# 60W_24V_to_12V_Flyback.net
KiCad netlist of a schematic drawn in EAGLE
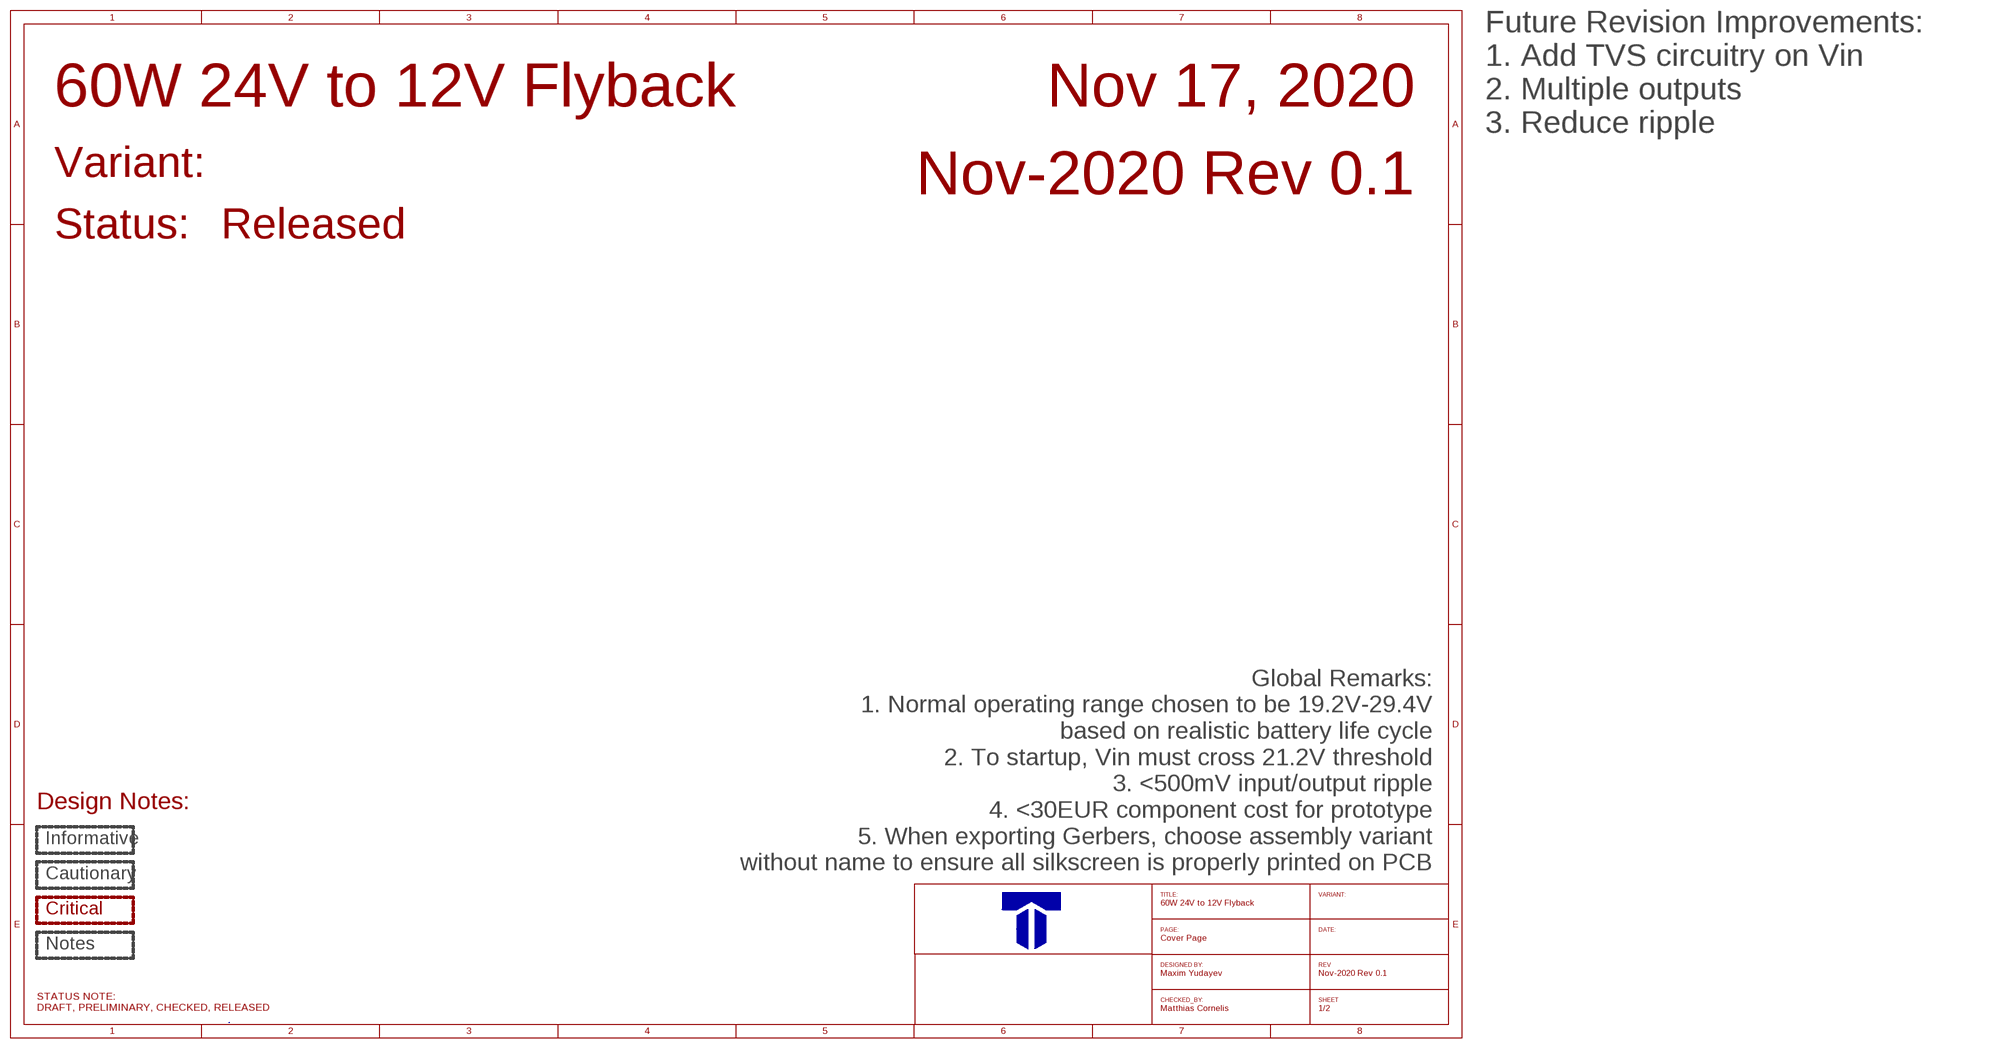
[diagram p0: schematic, sheet 1]
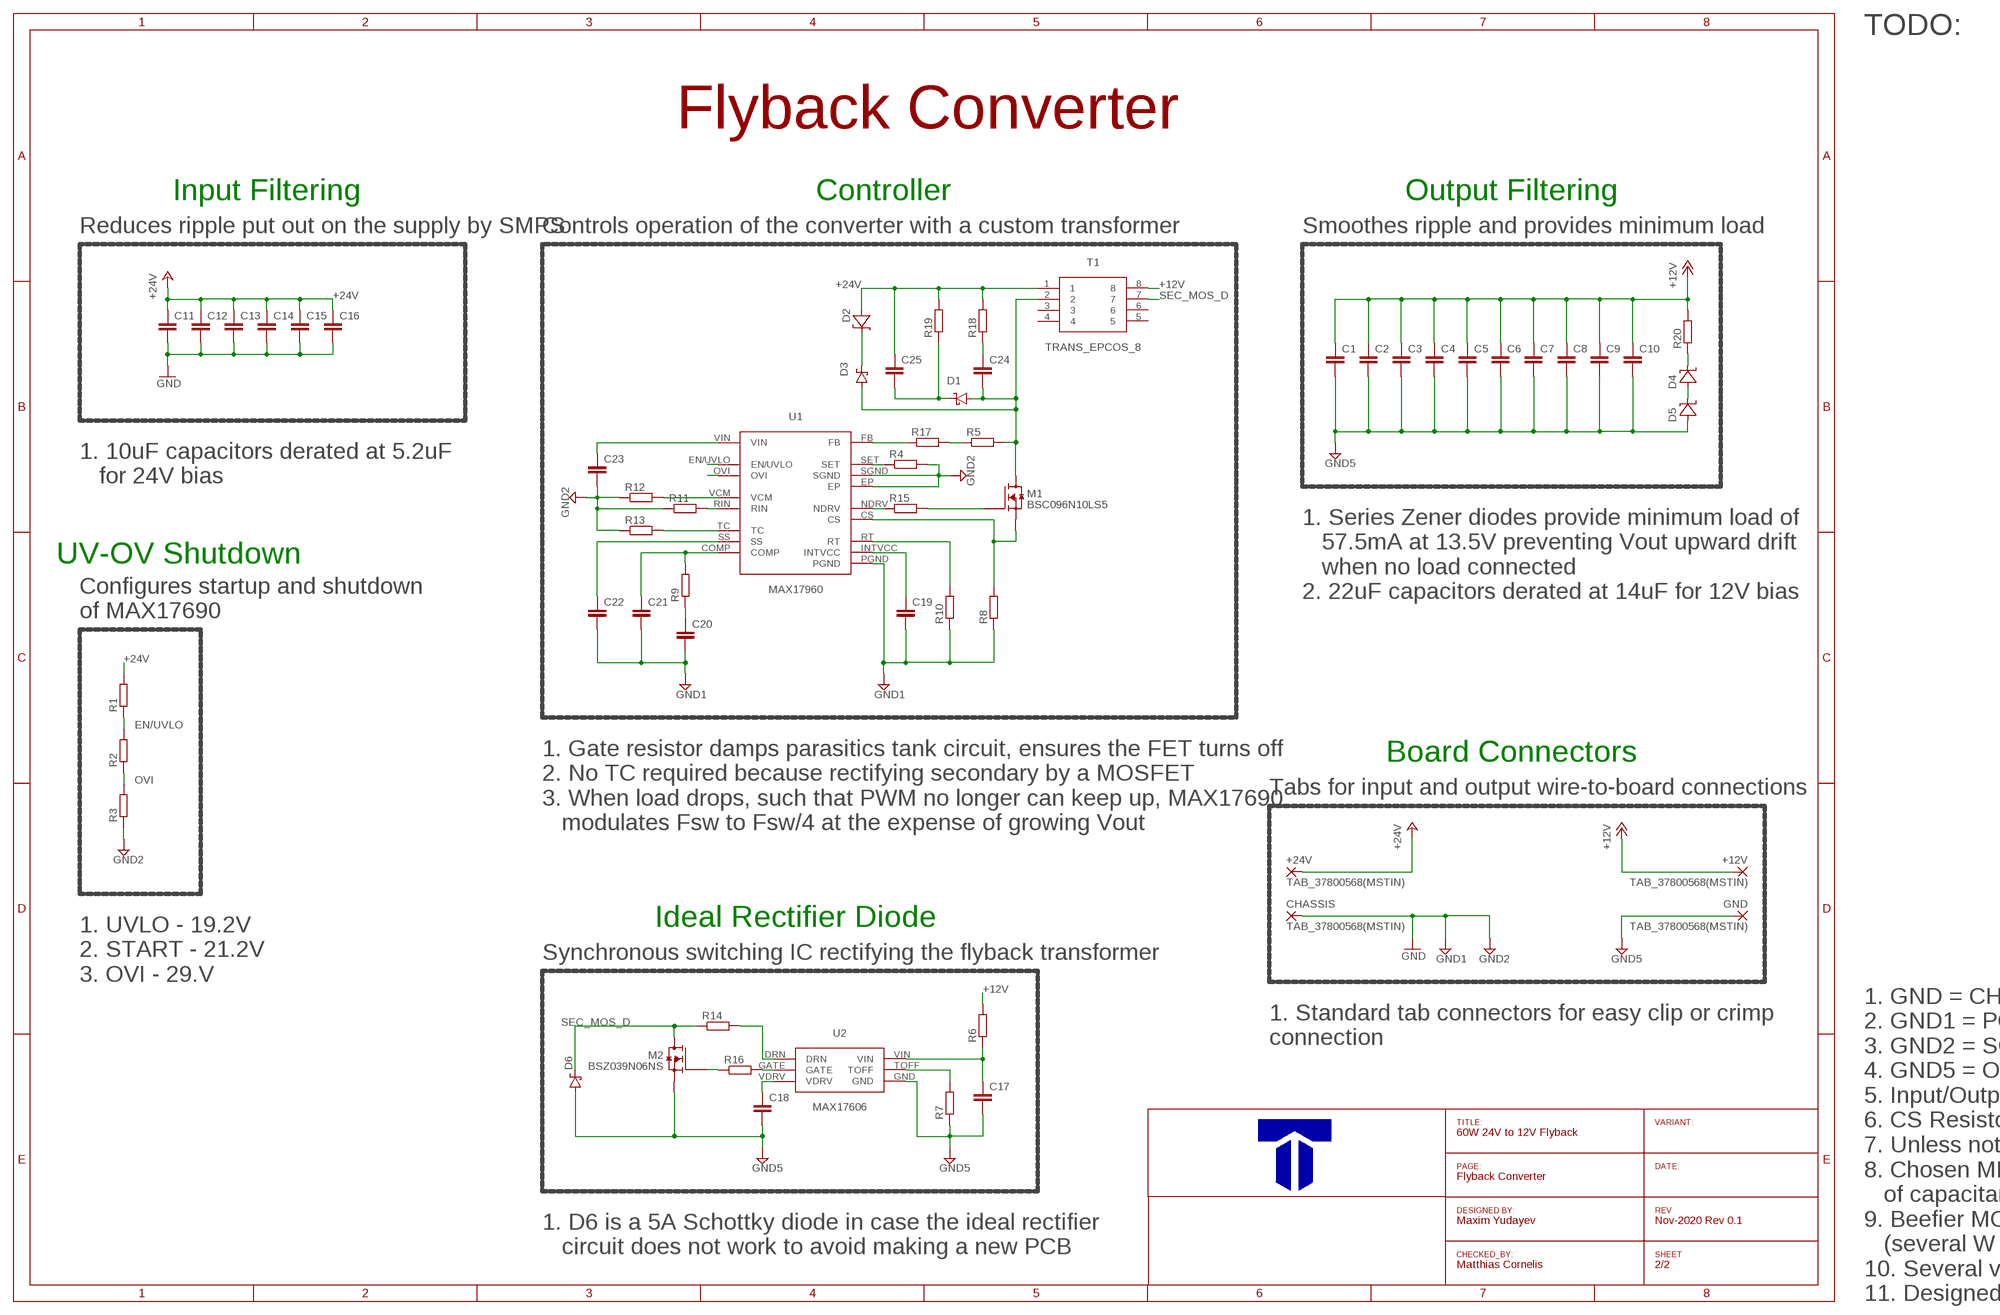
[diagram p1: schematic, sheet 2, part 1 of 2]
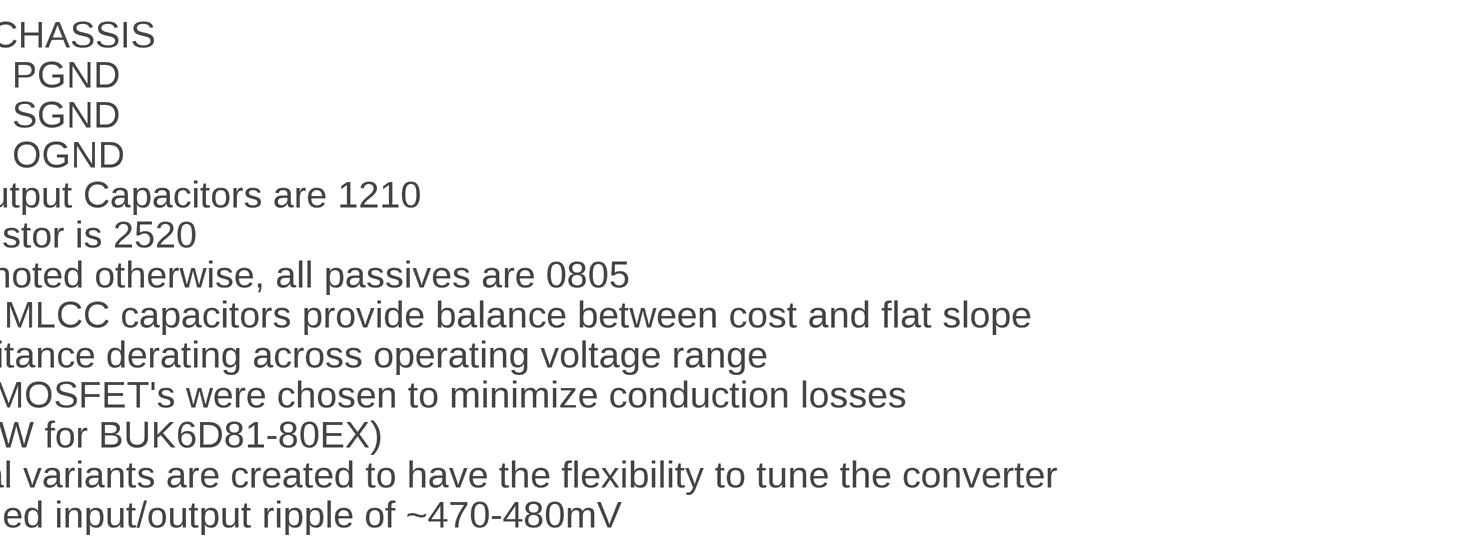
[diagram p2: schematic, sheet 2, part 2 of 2]

(export (version "E")
  (design (tool "Eeschema 10.0.6"))
  (components
    (comp (ref "+12V")
      (value "TAB_37800568(MSTIN)")
      (footprint "eagle-import:HOLE_1-3")
      (libsource (lib "eagle-import") (part "TAB_37800568(MSTIN)"))
    )
    (comp (ref "+24V")
      (value "TAB_37800568(MSTIN)")
      (footprint "eagle-import:HOLE_1-3")
      (libsource (lib "eagle-import") (part "TAB_37800568(MSTIN)"))
    )
    (comp (ref "C1")
      (value "C-EUC1210K")
      (footprint "eagle-import:C1210K")
      (libsource (lib "eagle-import") (part "C-EUC1210K"))
    )
    (comp (ref "C2")
      (value "C-EUC1210K")
      (footprint "eagle-import:C1210K")
      (libsource (lib "eagle-import") (part "C-EUC1210K"))
    )
    (comp (ref "C3")
      (value "C-EUC1210K")
      (footprint "eagle-import:C1210K")
      (libsource (lib "eagle-import") (part "C-EUC1210K"))
    )
    (comp (ref "C4")
      (value "C-EUC1210K")
      (footprint "eagle-import:C1210K")
      (libsource (lib "eagle-import") (part "C-EUC1210K"))
    )
    (comp (ref "C5")
      (value "C-EUC1210K")
      (footprint "eagle-import:C1210K")
      (libsource (lib "eagle-import") (part "C-EUC1210K"))
    )
    (comp (ref "C6")
      (value "C-EUC1210K")
      (footprint "eagle-import:C1210K")
      (libsource (lib "eagle-import") (part "C-EUC1210K"))
    )
    (comp (ref "C7")
      (value "C-EUC1210K")
      (footprint "eagle-import:C1210K")
      (libsource (lib "eagle-import") (part "C-EUC1210K"))
    )
    (comp (ref "C8")
      (value "C-EUC1210K")
      (footprint "eagle-import:C1210K")
      (libsource (lib "eagle-import") (part "C-EUC1210K"))
    )
    (comp (ref "C9")
      (value "C-EUC1210K")
      (footprint "eagle-import:C1210K")
      (libsource (lib "eagle-import") (part "C-EUC1210K"))
    )
    (comp (ref "C10")
      (value "C-EUC1210K")
      (footprint "eagle-import:C1210K")
      (libsource (lib "eagle-import") (part "C-EUC1210K"))
    )
    (comp (ref "C11")
      (value "C-EUC1210K")
      (footprint "eagle-import:C1210K")
      (libsource (lib "eagle-import") (part "C-EUC1210K"))
    )
    (comp (ref "C12")
      (value "C-EUC1210K")
      (footprint "eagle-import:C1210K")
      (libsource (lib "eagle-import") (part "C-EUC1210K"))
    )
    (comp (ref "C13")
      (value "C-EUC1210K")
      (footprint "eagle-import:C1210K")
      (libsource (lib "eagle-import") (part "C-EUC1210K"))
    )
    (comp (ref "C14")
      (value "C-EUC1210K")
      (footprint "eagle-import:C1210K")
      (libsource (lib "eagle-import") (part "C-EUC1210K"))
    )
    (comp (ref "C15")
      (value "C-EUC1210K")
      (footprint "eagle-import:C1210K")
      (libsource (lib "eagle-import") (part "C-EUC1210K"))
    )
    (comp (ref "C16")
      (value "C-EUC1210K")
      (footprint "eagle-import:C1210K")
      (libsource (lib "eagle-import") (part "C-EUC1210K"))
    )
    (comp (ref "C17")
      (value "C-EUC0805K")
      (footprint "eagle-import:C0805K")
      (libsource (lib "eagle-import") (part "C-EUC0805K"))
    )
    (comp (ref "C18")
      (value "C-EUC0805K")
      (footprint "eagle-import:C0805K")
      (libsource (lib "eagle-import") (part "C-EUC0805K"))
    )
    (comp (ref "C19")
      (value "C-EUC0805K")
      (footprint "eagle-import:C0805K")
      (libsource (lib "eagle-import") (part "C-EUC0805K"))
    )
    (comp (ref "C20")
      (value "C-EUC0805K")
      (footprint "eagle-import:C0805K")
      (libsource (lib "eagle-import") (part "C-EUC0805K"))
    )
    (comp (ref "C21")
      (value "C-EUC0805K")
      (footprint "eagle-import:C0805K")
      (libsource (lib "eagle-import") (part "C-EUC0805K"))
    )
    (comp (ref "C22")
      (value "C-EUC0805K")
      (footprint "eagle-import:C0805K")
      (libsource (lib "eagle-import") (part "C-EUC0805K"))
    )
    (comp (ref "C23")
      (value "C-EUC0805K")
      (footprint "eagle-import:C0805K")
      (libsource (lib "eagle-import") (part "C-EUC0805K"))
    )
    (comp (ref "C24")
      (value "C-EUC0805K")
      (footprint "eagle-import:C0805K")
      (libsource (lib "eagle-import") (part "C-EUC0805K"))
    )
    (comp (ref "C25")
      (value "C-EUC0805K")
      (footprint "eagle-import:C0805K")
      (libsource (lib "eagle-import") (part "C-EUC0805K"))
    )
    (comp (ref "CHASSIS")
      (value "TAB_37800568(MSTIN)")
      (footprint "eagle-import:HOLE_1-3")
      (libsource (lib "eagle-import") (part "TAB_37800568(MSTIN)"))
    )
    (comp (ref "D1")
      (value "DFLS2100-7")
      (footprint "eagle-import:DFLS2100_DS31475")
      (libsource (lib "eagle-import") (part "DFLS2100-7"))
    )
    (comp (ref "D2")
      (value "MMSZ5270BT1G")
      (footprint "eagle-import:MMSZ_T1G_SOD-123_425-04")
      (libsource (lib "eagle-import") (part "MMSZ52?T1G70B"))
    )
    (comp (ref "D3")
      (value "DFLS2100-7")
      (footprint "eagle-import:DFLS2100_DS31475")
      (libsource (lib "eagle-import") (part "DFLS2100-7"))
    )
    (comp (ref "D4")
      (value "MMSZ4692T1G")
      (footprint "eagle-import:MMSZ_T1G_SOD-123_425-04")
      (libsource (lib "eagle-import") (part "MMSZ4?T1G692"))
    )
    (comp (ref "D5")
      (value "MMSZ4692T1G")
      (footprint "eagle-import:MMSZ_T1G_SOD-123_425-04")
      (libsource (lib "eagle-import") (part "MMSZ4?T1G692"))
    )
    (comp (ref "D6")
      (value "B540C-13-F")
      (footprint "eagle-import:B5_0C-13-F_DO-214AB_DS13012")
      (libsource (lib "eagle-import") (part "B5?0C-13-F4"))
    )
    (comp (ref "GND")
      (value "TAB_37800568(MSTIN)")
      (footprint "eagle-import:HOLE_1-3")
      (libsource (lib "eagle-import") (part "TAB_37800568(MSTIN)"))
    )
    (comp (ref "M1")
      (value "BSC096N10LS5")
      (footprint "eagle-import:BSC096N10LS5_TDSON-8")
      (libsource (lib "eagle-import") (part "BSC096N10LS5"))
    )
    (comp (ref "M2")
      (value "BSZ039N06NS")
      (footprint "eagle-import:BSZ039N06NS_TSDSON-8_Z8B00158553")
      (libsource (lib "eagle-import") (part "BSZ039N06NS"))
    )
    (comp (ref "R1")
      (value "R-EU_R0805")
      (footprint "eagle-import:R0805")
      (libsource (lib "eagle-import") (part "R-EU_R0805"))
    )
    (comp (ref "R2")
      (value "R-EU_R0805")
      (footprint "eagle-import:R0805")
      (libsource (lib "eagle-import") (part "R-EU_R0805"))
    )
    (comp (ref "R3")
      (value "R-EU_R0805")
      (footprint "eagle-import:R0805")
      (libsource (lib "eagle-import") (part "R-EU_R0805"))
    )
    (comp (ref "R4")
      (value "R-EU_R0805")
      (footprint "eagle-import:R0805")
      (libsource (lib "eagle-import") (part "R-EU_R0805"))
    )
    (comp (ref "R5")
      (value "R-EU_R0805")
      (footprint "eagle-import:R0805")
      (libsource (lib "eagle-import") (part "R-EU_R0805"))
    )
    (comp (ref "R6")
      (value "R-EU_R0805")
      (footprint "eagle-import:R0805")
      (libsource (lib "eagle-import") (part "R-EU_R0805"))
    )
    (comp (ref "R7")
      (value "R-EU_R0805")
      (footprint "eagle-import:R0805")
      (libsource (lib "eagle-import") (part "R-EU_R0805"))
    )
    (comp (ref "R8")
      (value "R-EU_R2512")
      (footprint "eagle-import:R2512")
      (libsource (lib "eagle-import") (part "R-EU_R2512"))
    )
    (comp (ref "R9")
      (value "R-EU_R0805")
      (footprint "eagle-import:R0805")
      (libsource (lib "eagle-import") (part "R-EU_R0805"))
    )
    (comp (ref "R10")
      (value "R-EU_R0805")
      (footprint "eagle-import:R0805")
      (libsource (lib "eagle-import") (part "R-EU_R0805"))
    )
    (comp (ref "R11")
      (value "R-EU_R0805")
      (footprint "eagle-import:R0805")
      (libsource (lib "eagle-import") (part "R-EU_R0805"))
    )
    (comp (ref "R12")
      (value "R-EU_R0805")
      (footprint "eagle-import:R0805")
      (libsource (lib "eagle-import") (part "R-EU_R0805"))
    )
    (comp (ref "R13")
      (value "R-EU_R0805")
      (footprint "eagle-import:R0805")
      (libsource (lib "eagle-import") (part "R-EU_R0805"))
    )
    (comp (ref "R14")
      (value "R-EU_R0805")
      (footprint "eagle-import:R0805")
      (libsource (lib "eagle-import") (part "R-EU_R0805"))
    )
    (comp (ref "R15")
      (value "R-EU_R0805")
      (footprint "eagle-import:R0805")
      (libsource (lib "eagle-import") (part "R-EU_R0805"))
    )
    (comp (ref "R16")
      (value "R-EU_R0805")
      (footprint "eagle-import:R0805")
      (libsource (lib "eagle-import") (part "R-EU_R0805"))
    )
    (comp (ref "R17")
      (value "R-EU_R0805")
      (footprint "eagle-import:R0805")
      (libsource (lib "eagle-import") (part "R-EU_R0805"))
    )
    (comp (ref "R18")
      (value "R-EU_R0805")
      (footprint "eagle-import:R0805")
      (libsource (lib "eagle-import") (part "R-EU_R0805"))
    )
    (comp (ref "R19")
      (value "R-EU_R0805")
      (footprint "eagle-import:R0805")
      (libsource (lib "eagle-import") (part "R-EU_R0805"))
    )
    (comp (ref "R20")
      (value "R-EU_R0805")
      (footprint "eagle-import:R0805")
      (libsource (lib "eagle-import") (part "R-EU_R0805"))
    )
    (comp (ref "T1")
      (value "TRANS_EPCOS_8")
      (footprint "eagle-import:TRANS_EPCOS-B66307_E16_8_5_0.5_3.45UH_200K")
      (libsource (lib "eagle-import") (part "TRANS_EPCOS_8"))
    )
    (comp (ref "U1")
      (value "MAX17960")
      (footprint "eagle-import:T1633-4")
      (libsource (lib "eagle-import") (part "MAX17960"))
    )
    (comp (ref "U2")
      (value "MAX17606")
      (footprint "eagle-import:MAX17606_90-0242")
      (libsource (lib "eagle-import") (part "MAX17606"))
    )
  )
  (nets
    (net (code "1") (name "+12V") (class "Default")
      (node (ref "+12V") (pin "P$1") (pinfunction "P_P$1") (pintype "passive"))
      (node (ref "C1") (pin "1") (pinfunction "1_1") (pintype "passive"))
      (node (ref "C10") (pin "1") (pinfunction "1_1") (pintype "passive"))
      (node (ref "C2") (pin "1") (pinfunction "1_1") (pintype "passive"))
      (node (ref "C3") (pin "1") (pinfunction "1_1") (pintype "passive"))
      (node (ref "C4") (pin "1") (pinfunction "1_1") (pintype "passive"))
      (node (ref "C5") (pin "1") (pinfunction "1_1") (pintype "passive"))
      (node (ref "C6") (pin "1") (pinfunction "1_1") (pintype "passive"))
      (node (ref "C7") (pin "1") (pinfunction "1_1") (pintype "passive"))
      (node (ref "C8") (pin "1") (pinfunction "1_1") (pintype "passive"))
      (node (ref "C9") (pin "1") (pinfunction "1_1") (pintype "passive"))
      (node (ref "R20") (pin "2") (pinfunction "2_2") (pintype "passive"))
      (node (ref "R6") (pin "2") (pinfunction "2_2") (pintype "passive"))
      (node (ref "T1") (pin "8") (pinfunction "8_8") (pintype "bidirectional"))
    )
    (net (code "2") (name "+24V") (class "Default")
      (node (ref "+24V") (pin "P$1") (pinfunction "P_P$1") (pintype "passive"))
      (node (ref "C11") (pin "1") (pinfunction "1_1") (pintype "passive"))
      (node (ref "C12") (pin "1") (pinfunction "1_1") (pintype "passive"))
      (node (ref "C13") (pin "1") (pinfunction "1_1") (pintype "passive"))
      (node (ref "C14") (pin "1") (pinfunction "1_1") (pintype "passive"))
      (node (ref "C15") (pin "1") (pinfunction "1_1") (pintype "passive"))
      (node (ref "C16") (pin "1") (pinfunction "1_1") (pintype "passive"))
      (node (ref "C23") (pin "1") (pinfunction "1_1") (pintype "passive"))
      (node (ref "C25") (pin "1") (pinfunction "1_1") (pintype "passive"))
      (node (ref "D2") (pin "A") (pinfunction "A_A") (pintype "passive"))
      (node (ref "R1") (pin "2") (pinfunction "2_2") (pintype "passive"))
      (node (ref "R18") (pin "2") (pinfunction "2_2") (pintype "passive"))
      (node (ref "R19") (pin "2") (pinfunction "2_2") (pintype "passive"))
      (node (ref "T1") (pin "1") (pinfunction "1_1") (pintype "bidirectional"))
      (node (ref "U1") (pin "VIN") (pinfunction "VIN_VIN") (pintype "power_in"))
    )
    (net (code "3") (name "EN{slash}UVLO") (class "Default")
      (node (ref "R1") (pin "1") (pinfunction "1_1") (pintype "passive"))
      (node (ref "R2") (pin "2") (pinfunction "2_2") (pintype "passive"))
      (node (ref "U1") (pin "EN/UVLO") (pinfunction "EN/UVLO_EN/UVLO") (pintype "input"))
    )
    (net (code "4") (name "GND") (class "Default")
      (node (ref "C11") (pin "2") (pinfunction "2_2") (pintype "passive"))
      (node (ref "C12") (pin "2") (pinfunction "2_2") (pintype "passive"))
      (node (ref "C13") (pin "2") (pinfunction "2_2") (pintype "passive"))
      (node (ref "C14") (pin "2") (pinfunction "2_2") (pintype "passive"))
      (node (ref "C15") (pin "2") (pinfunction "2_2") (pintype "passive"))
      (node (ref "C16") (pin "2") (pinfunction "2_2") (pintype "passive"))
      (node (ref "C19") (pin "2") (pinfunction "2_2") (pintype "passive"))
      (node (ref "C20") (pin "2") (pinfunction "2_2") (pintype "passive"))
      (node (ref "C21") (pin "2") (pinfunction "2_2") (pintype "passive"))
      (node (ref "C22") (pin "2") (pinfunction "2_2") (pintype "passive"))
      (node (ref "C23") (pin "2") (pinfunction "2_2") (pintype "passive"))
      (node (ref "CHASSIS") (pin "P$1") (pinfunction "P_P$1") (pintype "passive"))
      (node (ref "R10") (pin "1") (pinfunction "1_1") (pintype "passive"))
      (node (ref "R11") (pin "1") (pinfunction "1_1") (pintype "passive"))
      (node (ref "R12") (pin "1") (pinfunction "1_1") (pintype "passive"))
      (node (ref "R13") (pin "1") (pinfunction "1_1") (pintype "passive"))
      (node (ref "R3") (pin "1") (pinfunction "1_1") (pintype "passive"))
      (node (ref "R4") (pin "2") (pinfunction "2_2") (pintype "passive"))
      (node (ref "R8") (pin "1") (pinfunction "1_1") (pintype "passive"))
      (node (ref "U1") (pin "EP") (pinfunction "EP_EP") (pintype "power_in"))
      (node (ref "U1") (pin "PGND") (pinfunction "PGND_PGND") (pintype "power_in"))
      (node (ref "U1") (pin "SGND") (pinfunction "SGND_SGND") (pintype "power_in"))
    )
    (net (code "5") (name "GND5") (class "Default")
      (node (ref "C1") (pin "2") (pinfunction "2_2") (pintype "passive"))
      (node (ref "C10") (pin "2") (pinfunction "2_2") (pintype "passive"))
      (node (ref "C17") (pin "2") (pinfunction "2_2") (pintype "passive"))
      (node (ref "C18") (pin "2") (pinfunction "2_2") (pintype "passive"))
      (node (ref "C2") (pin "2") (pinfunction "2_2") (pintype "passive"))
      (node (ref "C3") (pin "2") (pinfunction "2_2") (pintype "passive"))
      (node (ref "C4") (pin "2") (pinfunction "2_2") (pintype "passive"))
      (node (ref "C5") (pin "2") (pinfunction "2_2") (pintype "passive"))
      (node (ref "C6") (pin "2") (pinfunction "2_2") (pintype "passive"))
      (node (ref "C7") (pin "2") (pinfunction "2_2") (pintype "passive"))
      (node (ref "C8") (pin "2") (pinfunction "2_2") (pintype "passive"))
      (node (ref "C9") (pin "2") (pinfunction "2_2") (pintype "passive"))
      (node (ref "D5") (pin "A") (pinfunction "A_A") (pintype "passive"))
      (node (ref "D6") (pin "A") (pinfunction "A_A") (pintype "passive"))
      (node (ref "GND") (pin "P$1") (pinfunction "P_P$1") (pintype "passive"))
      (node (ref "M2") (pin "S") (pinfunction "S_S") (pintype "passive"))
      (node (ref "R7") (pin "1") (pinfunction "1_1") (pintype "passive"))
      (node (ref "U2") (pin "GND") (pinfunction "GND_GND") (pintype "power_in"))
    )
    (net (code "6") (name "Net-(C17-Pad1)") (class "Default")
      (node (ref "C17") (pin "1") (pinfunction "1_1") (pintype "passive"))
      (node (ref "R6") (pin "1") (pinfunction "1_1") (pintype "passive"))
      (node (ref "U2") (pin "VIN") (pinfunction "VIN_VIN") (pintype "power_in"))
    )
    (net (code "7") (name "Net-(C18-Pad1)") (class "Default")
      (node (ref "C18") (pin "1") (pinfunction "1_1") (pintype "passive"))
      (node (ref "U2") (pin "VDRV") (pinfunction "VDRV_VDRV") (pintype "input"))
    )
    (net (code "8") (name "Net-(C19-Pad1)") (class "Default")
      (node (ref "C19") (pin "1") (pinfunction "1_1") (pintype "passive"))
      (node (ref "U1") (pin "INTVCC") (pinfunction "INTVCC_INTVCC") (pintype "input"))
    )
    (net (code "9") (name "Net-(C20-Pad1)") (class "Default")
      (node (ref "C20") (pin "1") (pinfunction "1_1") (pintype "passive"))
      (node (ref "R9") (pin "1") (pinfunction "1_1") (pintype "passive"))
    )
    (net (code "10") (name "Net-(C21-Pad1)") (class "Default")
      (node (ref "C21") (pin "1") (pinfunction "1_1") (pintype "passive"))
      (node (ref "R9") (pin "2") (pinfunction "2_2") (pintype "passive"))
      (node (ref "U1") (pin "COMP") (pinfunction "COMP_COMP") (pintype "output"))
    )
    (net (code "11") (name "Net-(C22-Pad1)") (class "Default")
      (node (ref "C22") (pin "1") (pinfunction "1_1") (pintype "passive"))
      (node (ref "U1") (pin "SS") (pinfunction "SS_SS") (pintype "bidirectional"))
    )
    (net (code "12") (name "Net-(C24-Pad1)") (class "Default")
      (node (ref "C24") (pin "1") (pinfunction "1_1") (pintype "passive"))
      (node (ref "R18") (pin "1") (pinfunction "1_1") (pintype "passive"))
    )
    (net (code "13") (name "Net-(C24-Pad2)") (class "Default")
      (node (ref "C24") (pin "2") (pinfunction "2_2") (pintype "passive"))
      (node (ref "D1") (pin "A") (pinfunction "A_A") (pintype "passive"))
      (node (ref "D3") (pin "A") (pinfunction "A_A") (pintype "passive"))
      (node (ref "M1") (pin "D") (pinfunction "D_D") (pintype "passive"))
      (node (ref "R5") (pin "2") (pinfunction "2_2") (pintype "passive"))
      (node (ref "T1") (pin "2") (pinfunction "2_2") (pintype "bidirectional"))
    )
    (net (code "14") (name "Net-(D1-K)") (class "Default")
      (node (ref "C25") (pin "2") (pinfunction "2_2") (pintype "passive"))
      (node (ref "D1") (pin "C") (pinfunction "K_C") (pintype "passive"))
      (node (ref "R19") (pin "1") (pinfunction "1_1") (pintype "passive"))
    )
    (net (code "15") (name "Net-(D3-K)") (class "Default")
      (node (ref "D2") (pin "C") (pinfunction "C_C") (pintype "passive"))
      (node (ref "D3") (pin "C") (pinfunction "K_C") (pintype "passive"))
    )
    (net (code "16") (name "Net-(D4-PadA)") (class "Default")
      (node (ref "D4") (pin "A") (pinfunction "A_A") (pintype "passive"))
      (node (ref "D5") (pin "C") (pinfunction "C_C") (pintype "passive"))
    )
    (net (code "17") (name "Net-(D4-PadC)") (class "Default")
      (node (ref "D4") (pin "C") (pinfunction "C_C") (pintype "passive"))
      (node (ref "R20") (pin "1") (pinfunction "1_1") (pintype "passive"))
    )
    (net (code "18") (name "Net-(M1-PadG)") (class "Default")
      (node (ref "M1") (pin "G") (pinfunction "G_G") (pintype "passive"))
      (node (ref "R15") (pin "2") (pinfunction "2_2") (pintype "passive"))
    )
    (net (code "19") (name "Net-(M1-PadS)") (class "Default")
      (node (ref "M1") (pin "S") (pinfunction "S_S") (pintype "passive"))
      (node (ref "R8") (pin "2") (pinfunction "2_2") (pintype "passive"))
      (node (ref "U1") (pin "CS") (pinfunction "CS_CS") (pintype "input"))
    )
    (net (code "20") (name "Net-(M2-PadG)") (class "Default")
      (node (ref "M2") (pin "G") (pinfunction "G_G") (pintype "passive"))
      (node (ref "R16") (pin "1") (pinfunction "1_1") (pintype "passive"))
    )
    (net (code "21") (name "Net-(R4-Pad1)") (class "Default")
      (node (ref "R4") (pin "1") (pinfunction "1_1") (pintype "passive"))
      (node (ref "U1") (pin "SET") (pinfunction "SET_SET") (pintype "input"))
    )
    (net (code "22") (name "Net-(R7-Pad2)") (class "Default")
      (node (ref "R7") (pin "2") (pinfunction "2_2") (pintype "passive"))
      (node (ref "U2") (pin "TOFF") (pinfunction "TOFF_TOFF") (pintype "bidirectional"))
    )
    (net (code "23") (name "Net-(R10-Pad2)") (class "Default")
      (node (ref "R10") (pin "2") (pinfunction "2_2") (pintype "passive"))
      (node (ref "U1") (pin "RT") (pinfunction "RT_RT") (pintype "bidirectional"))
    )
    (net (code "24") (name "Net-(R11-Pad2)") (class "Default")
      (node (ref "R11") (pin "2") (pinfunction "2_2") (pintype "passive"))
      (node (ref "U1") (pin "RIN") (pinfunction "RIN_RIN") (pintype "bidirectional"))
    )
    (net (code "25") (name "Net-(R12-Pad2)") (class "Default")
      (node (ref "R12") (pin "2") (pinfunction "2_2") (pintype "passive"))
      (node (ref "U1") (pin "VCM") (pinfunction "VCM_VCM") (pintype "input"))
    )
    (net (code "26") (name "Net-(R13-Pad2)") (class "Default")
      (node (ref "R13") (pin "2") (pinfunction "2_2") (pintype "passive"))
      (node (ref "U1") (pin "TC") (pinfunction "TC_TC") (pintype "output"))
    )
    (net (code "27") (name "Net-(R14-Pad2)") (class "Default")
      (node (ref "R14") (pin "2") (pinfunction "2_2") (pintype "passive"))
      (node (ref "U2") (pin "DRN") (pinfunction "DRN_DRN") (pintype "input"))
    )
    (net (code "28") (name "Net-(R15-Pad1)") (class "Default")
      (node (ref "R15") (pin "1") (pinfunction "1_1") (pintype "passive"))
      (node (ref "U1") (pin "NDRV") (pinfunction "NDRV_NDRV") (pintype "output"))
    )
    (net (code "29") (name "Net-(R16-Pad2)") (class "Default")
      (node (ref "R16") (pin "2") (pinfunction "2_2") (pintype "passive"))
      (node (ref "U2") (pin "GATE") (pinfunction "GATE_GATE") (pintype "output"))
    )
    (net (code "30") (name "Net-(R17-Pad1)") (class "Default")
      (node (ref "R17") (pin "1") (pinfunction "1_1") (pintype "passive"))
      (node (ref "U1") (pin "FB") (pinfunction "FB_FB") (pintype "input"))
    )
    (net (code "31") (name "Net-(R17-Pad2)") (class "Default")
      (node (ref "R17") (pin "2") (pinfunction "2_2") (pintype "passive"))
      (node (ref "R5") (pin "1") (pinfunction "1_1") (pintype "passive"))
    )
    (net (code "32") (name "OVI") (class "Default")
      (node (ref "R2") (pin "1") (pinfunction "1_1") (pintype "passive"))
      (node (ref "R3") (pin "2") (pinfunction "2_2") (pintype "passive"))
      (node (ref "U1") (pin "OVI") (pinfunction "OVI_OVI") (pintype "input"))
    )
    (net (code "33") (name "SEC_MOS_D") (class "Default")
      (node (ref "D6") (pin "C") (pinfunction "K_C") (pintype "passive"))
      (node (ref "M2") (pin "D") (pinfunction "D_D") (pintype "passive"))
      (node (ref "R14") (pin "1") (pinfunction "1_1") (pintype "passive"))
      (node (ref "T1") (pin "7") (pinfunction "7_7") (pintype "bidirectional"))
    )
    (net (code "34") (name "unconnected-(T1-Pad3)") (class "Default")
      (node (ref "T1") (pin "3") (pinfunction "3_3") (pintype "bidirectional"))
    )
    (net (code "35") (name "unconnected-(T1-Pad4)") (class "Default")
      (node (ref "T1") (pin "4") (pinfunction "4_4") (pintype "bidirectional"))
    )
    (net (code "36") (name "unconnected-(T1-Pad5)") (class "Default")
      (node (ref "T1") (pin "5") (pinfunction "5_5") (pintype "bidirectional"))
    )
    (net (code "37") (name "unconnected-(T1-Pad6)") (class "Default")
      (node (ref "T1") (pin "6") (pinfunction "6_6") (pintype "bidirectional"))
    )
  )
)
